# InterfacesWaveyRadar.net
KiCad netlist of a schematic drawn in Altium Designer
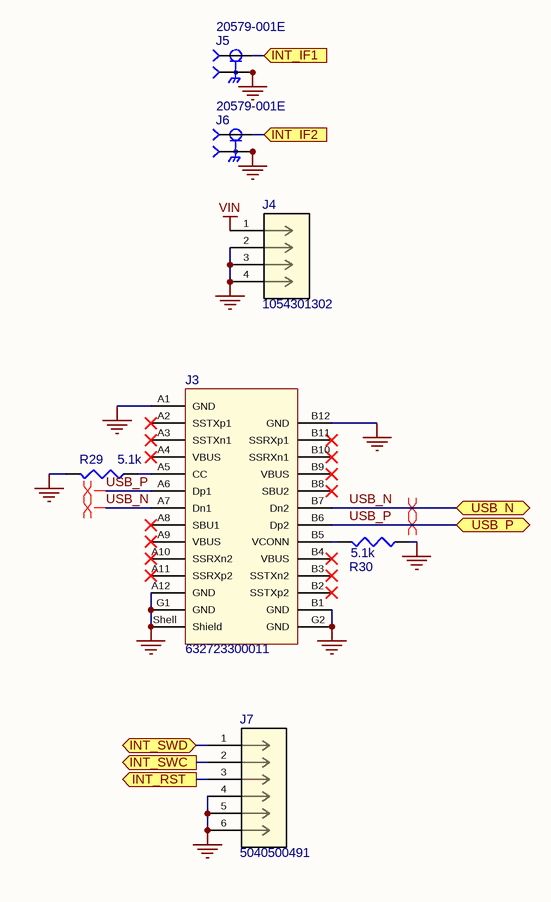
[diagram p0: InterfacesWaveyRadar.SchDoc]

(export (version "E")
  (design (tool "Eeschema 10.0.6"))
  (components
    (comp (ref "J3")
      (value "632723300011")
      (footprint "632723300011")
      (description "USB 3.1 Type C, Receptacle, Horizontal, THR")
      (fields (field (name "MANUFACTURER") "Wurth Elektronik"))
      (libsource (lib "University of South Florida") (part "Symbol"))
    )
    (comp (ref "J4")
      (value "1054301302")
      (footprint "CON_1054301302_MOL")
      (fields (field (name "COPYRIGHT") "Copyright (C) 2018 Accelerated Designs. All rights reserved"))
      (libsource (lib "University of South Florida") (part "1054301302"))
    )
    (comp (ref "J5")
      (value "20579-001E")
      (footprint "IPEX_20579-001E")
      (description "12GHz RF recepticle with lock")
      (fields (field (name "MF") "I-PEX"))
      (libsource (lib "University of South Florida") (part "20579-001E"))
    )
    (comp (ref "J6")
      (value "20579-001E")
      (footprint "IPEX_20579-001E")
      (description "12GHz RF recepticle with lock")
      (fields (field (name "MF") "I-PEX"))
      (libsource (lib "University of South Florida") (part "20579-001E"))
    )
    (comp (ref "J7")
      (value "5040500491")
      (footprint "CON_5040500491")
      (fields (field (name "COPYRIGHT") "Copyright (C) 2018 Accelerated Designs. All rights reserved"))
      (libsource (lib "University of South Florida") (part "5040500491"))
    )
    (comp (ref "R29")
      (value "5.1k")
      (footprint "RESC1005X40X25NL05T05")
      (fields (field (name "Comment") "ERJ-2RKF5101X"))
      (libsource (lib "University of South Florida") (part "ResistorSymbol"))
    )
    (comp (ref "R30")
      (value "5.1k")
      (footprint "RESC1005X40X25NL05T05")
      (fields (field (name "Comment") "ERJ-2RKF5101X"))
      (libsource (lib "University of South Florida") (part "ResistorSymbol"))
    )
  )
  (nets
    (net (code "1") (name "/INT_IF1") (class "Default")
      (node (ref "J5") (pin "1") (pinfunction "SIGNAL_1") (pintype "passive"))
    )
    (net (code "2") (name "/INT_IF2") (class "Default")
      (node (ref "J6") (pin "1") (pinfunction "SIGNAL_1") (pintype "passive"))
    )
    (net (code "3") (name "/INT_RST") (class "Default")
      (node (ref "J7") (pin "3") (pinfunction "3_3") (pintype "passive"))
    )
    (net (code "4") (name "/INT_SWC") (class "Default")
      (node (ref "J7") (pin "2") (pinfunction "2_2") (pintype "passive"))
    )
    (net (code "5") (name "/INT_SWD") (class "Default")
      (node (ref "J7") (pin "1") (pinfunction "1_1") (pintype "passive"))
    )
    (net (code "6") (name "/USB_N") (class "Default")
      (node (ref "J3") (pin "A7") (pinfunction "Dn1_A7") (pintype "passive"))
      (node (ref "J3") (pin "B7") (pinfunction "Dn2_B7") (pintype "passive"))
    )
    (net (code "7") (name "/USB_P") (class "Default")
      (node (ref "J3") (pin "A6") (pinfunction "Dp1_A6") (pintype "passive"))
      (node (ref "J3") (pin "B6") (pinfunction "Dp2_B6") (pintype "passive"))
    )
    (net (code "8") (name "GND") (class "Default")
      (node (ref "J3") (pin "A1") (pinfunction "GND_A1") (pintype "passive"))
      (node (ref "J3") (pin "A12") (pinfunction "GND_A12") (pintype "passive"))
      (node (ref "J3") (pin "B1") (pinfunction "GND_B1") (pintype "passive"))
      (node (ref "J3") (pin "B12") (pinfunction "GND_B12") (pintype "passive"))
      (node (ref "J3") (pin "G1") (pinfunction "GND_G1") (pintype "passive"))
      (node (ref "J3") (pin "G2") (pinfunction "GND_G2") (pintype "passive"))
      (node (ref "J3") (pin "Shell") (pinfunction "Shield_Shell") (pintype "passive"))
      (node (ref "J4") (pin "2") (pinfunction "2_2") (pintype "passive"))
      (node (ref "J4") (pin "3") (pinfunction "3_3") (pintype "passive"))
      (node (ref "J4") (pin "4") (pinfunction "4_4") (pintype "passive"))
      (node (ref "J5") (pin "G1") (pinfunction "GROUND_G1") (pintype "passive"))
      (node (ref "J5") (pin "G2") (pinfunction "GROUND_G2") (pintype "passive"))
      (node (ref "J5") (pin "G3") (pinfunction "GROUND_G3") (pintype "passive"))
      (node (ref "J6") (pin "G1") (pinfunction "GROUND_G1") (pintype "passive"))
      (node (ref "J6") (pin "G2") (pinfunction "GROUND_G2") (pintype "passive"))
      (node (ref "J6") (pin "G3") (pinfunction "GROUND_G3") (pintype "passive"))
      (node (ref "J7") (pin "4") (pinfunction "4_4") (pintype "passive"))
      (node (ref "J7") (pin "5") (pinfunction "5_5") (pintype "passive"))
      (node (ref "J7") (pin "6") (pinfunction "6_6") (pintype "passive"))
      (node (ref "R29") (pin "2") (pinfunction "2_2") (pintype "passive"))
      (node (ref "R30") (pin "1") (pinfunction "1_1") (pintype "passive"))
    )
    (net (code "9") (name "Net-(J3-CC)") (class "Default")
      (node (ref "J3") (pin "A5") (pinfunction "CC_A5") (pintype "passive"))
      (node (ref "R29") (pin "1") (pinfunction "1_1") (pintype "passive"))
    )
    (net (code "10") (name "Net-(J3-VCONN)") (class "Default")
      (node (ref "J3") (pin "B5") (pinfunction "VCONN_B5") (pintype "passive"))
      (node (ref "R30") (pin "2") (pinfunction "2_2") (pintype "passive"))
    )
    (net (code "11") (name "VIN") (class "Default")
      (node (ref "J4") (pin "1") (pinfunction "1_1") (pintype "passive"))
    )
    (net (code "12") (name "unconnected-(J3-SBU1-PadA8)") (class "Default")
      (node (ref "J3") (pin "A8") (pinfunction "SBU1_A8") (pintype "passive+no_connect"))
    )
    (net (code "13") (name "unconnected-(J3-SBU2-PadB8)") (class "Default")
      (node (ref "J3") (pin "B8") (pinfunction "SBU2_B8") (pintype "passive+no_connect"))
    )
    (net (code "14") (name "unconnected-(J3-SSRXn1-PadB10)") (class "Default")
      (node (ref "J3") (pin "B10") (pinfunction "SSRXn1_B10") (pintype "passive+no_connect"))
    )
    (net (code "15") (name "unconnected-(J3-SSRXn2-PadA10)") (class "Default")
      (node (ref "J3") (pin "A10") (pinfunction "SSRXn2_A10") (pintype "passive+no_connect"))
    )
    (net (code "16") (name "unconnected-(J3-SSRXp1-PadB11)") (class "Default")
      (node (ref "J3") (pin "B11") (pinfunction "SSRXp1_B11") (pintype "passive+no_connect"))
    )
    (net (code "17") (name "unconnected-(J3-SSRXp2-PadA11)") (class "Default")
      (node (ref "J3") (pin "A11") (pinfunction "SSRXp2_A11") (pintype "passive+no_connect"))
    )
    (net (code "18") (name "unconnected-(J3-SSTXn1-PadA3)") (class "Default")
      (node (ref "J3") (pin "A3") (pinfunction "SSTXn1_A3") (pintype "passive+no_connect"))
    )
    (net (code "19") (name "unconnected-(J3-SSTXn2-PadB3)") (class "Default")
      (node (ref "J3") (pin "B3") (pinfunction "SSTXn2_B3") (pintype "passive+no_connect"))
    )
    (net (code "20") (name "unconnected-(J3-SSTXp1-PadA2)") (class "Default")
      (node (ref "J3") (pin "A2") (pinfunction "SSTXp1_A2") (pintype "passive+no_connect"))
    )
    (net (code "21") (name "unconnected-(J3-SSTXp2-PadB2)") (class "Default")
      (node (ref "J3") (pin "B2") (pinfunction "SSTXp2_B2") (pintype "passive+no_connect"))
    )
    (net (code "22") (name "unconnected-(J3-VBUS-PadA4)") (class "Default")
      (node (ref "J3") (pin "A4") (pinfunction "VBUS_A4") (pintype "passive+no_connect"))
    )
    (net (code "23") (name "unconnected-(J3-VBUS-PadA9)") (class "Default")
      (node (ref "J3") (pin "A9") (pinfunction "VBUS_A9") (pintype "passive+no_connect"))
    )
    (net (code "24") (name "unconnected-(J3-VBUS-PadB4)") (class "Default")
      (node (ref "J3") (pin "B4") (pinfunction "VBUS_B4") (pintype "passive+no_connect"))
    )
    (net (code "25") (name "unconnected-(J3-VBUS-PadB9)") (class "Default")
      (node (ref "J3") (pin "B9") (pinfunction "VBUS_B9") (pintype "passive+no_connect"))
    )
  )
)
